# p3_mcu.net
KiCad netlist of a schematic drawn in Altium Designer
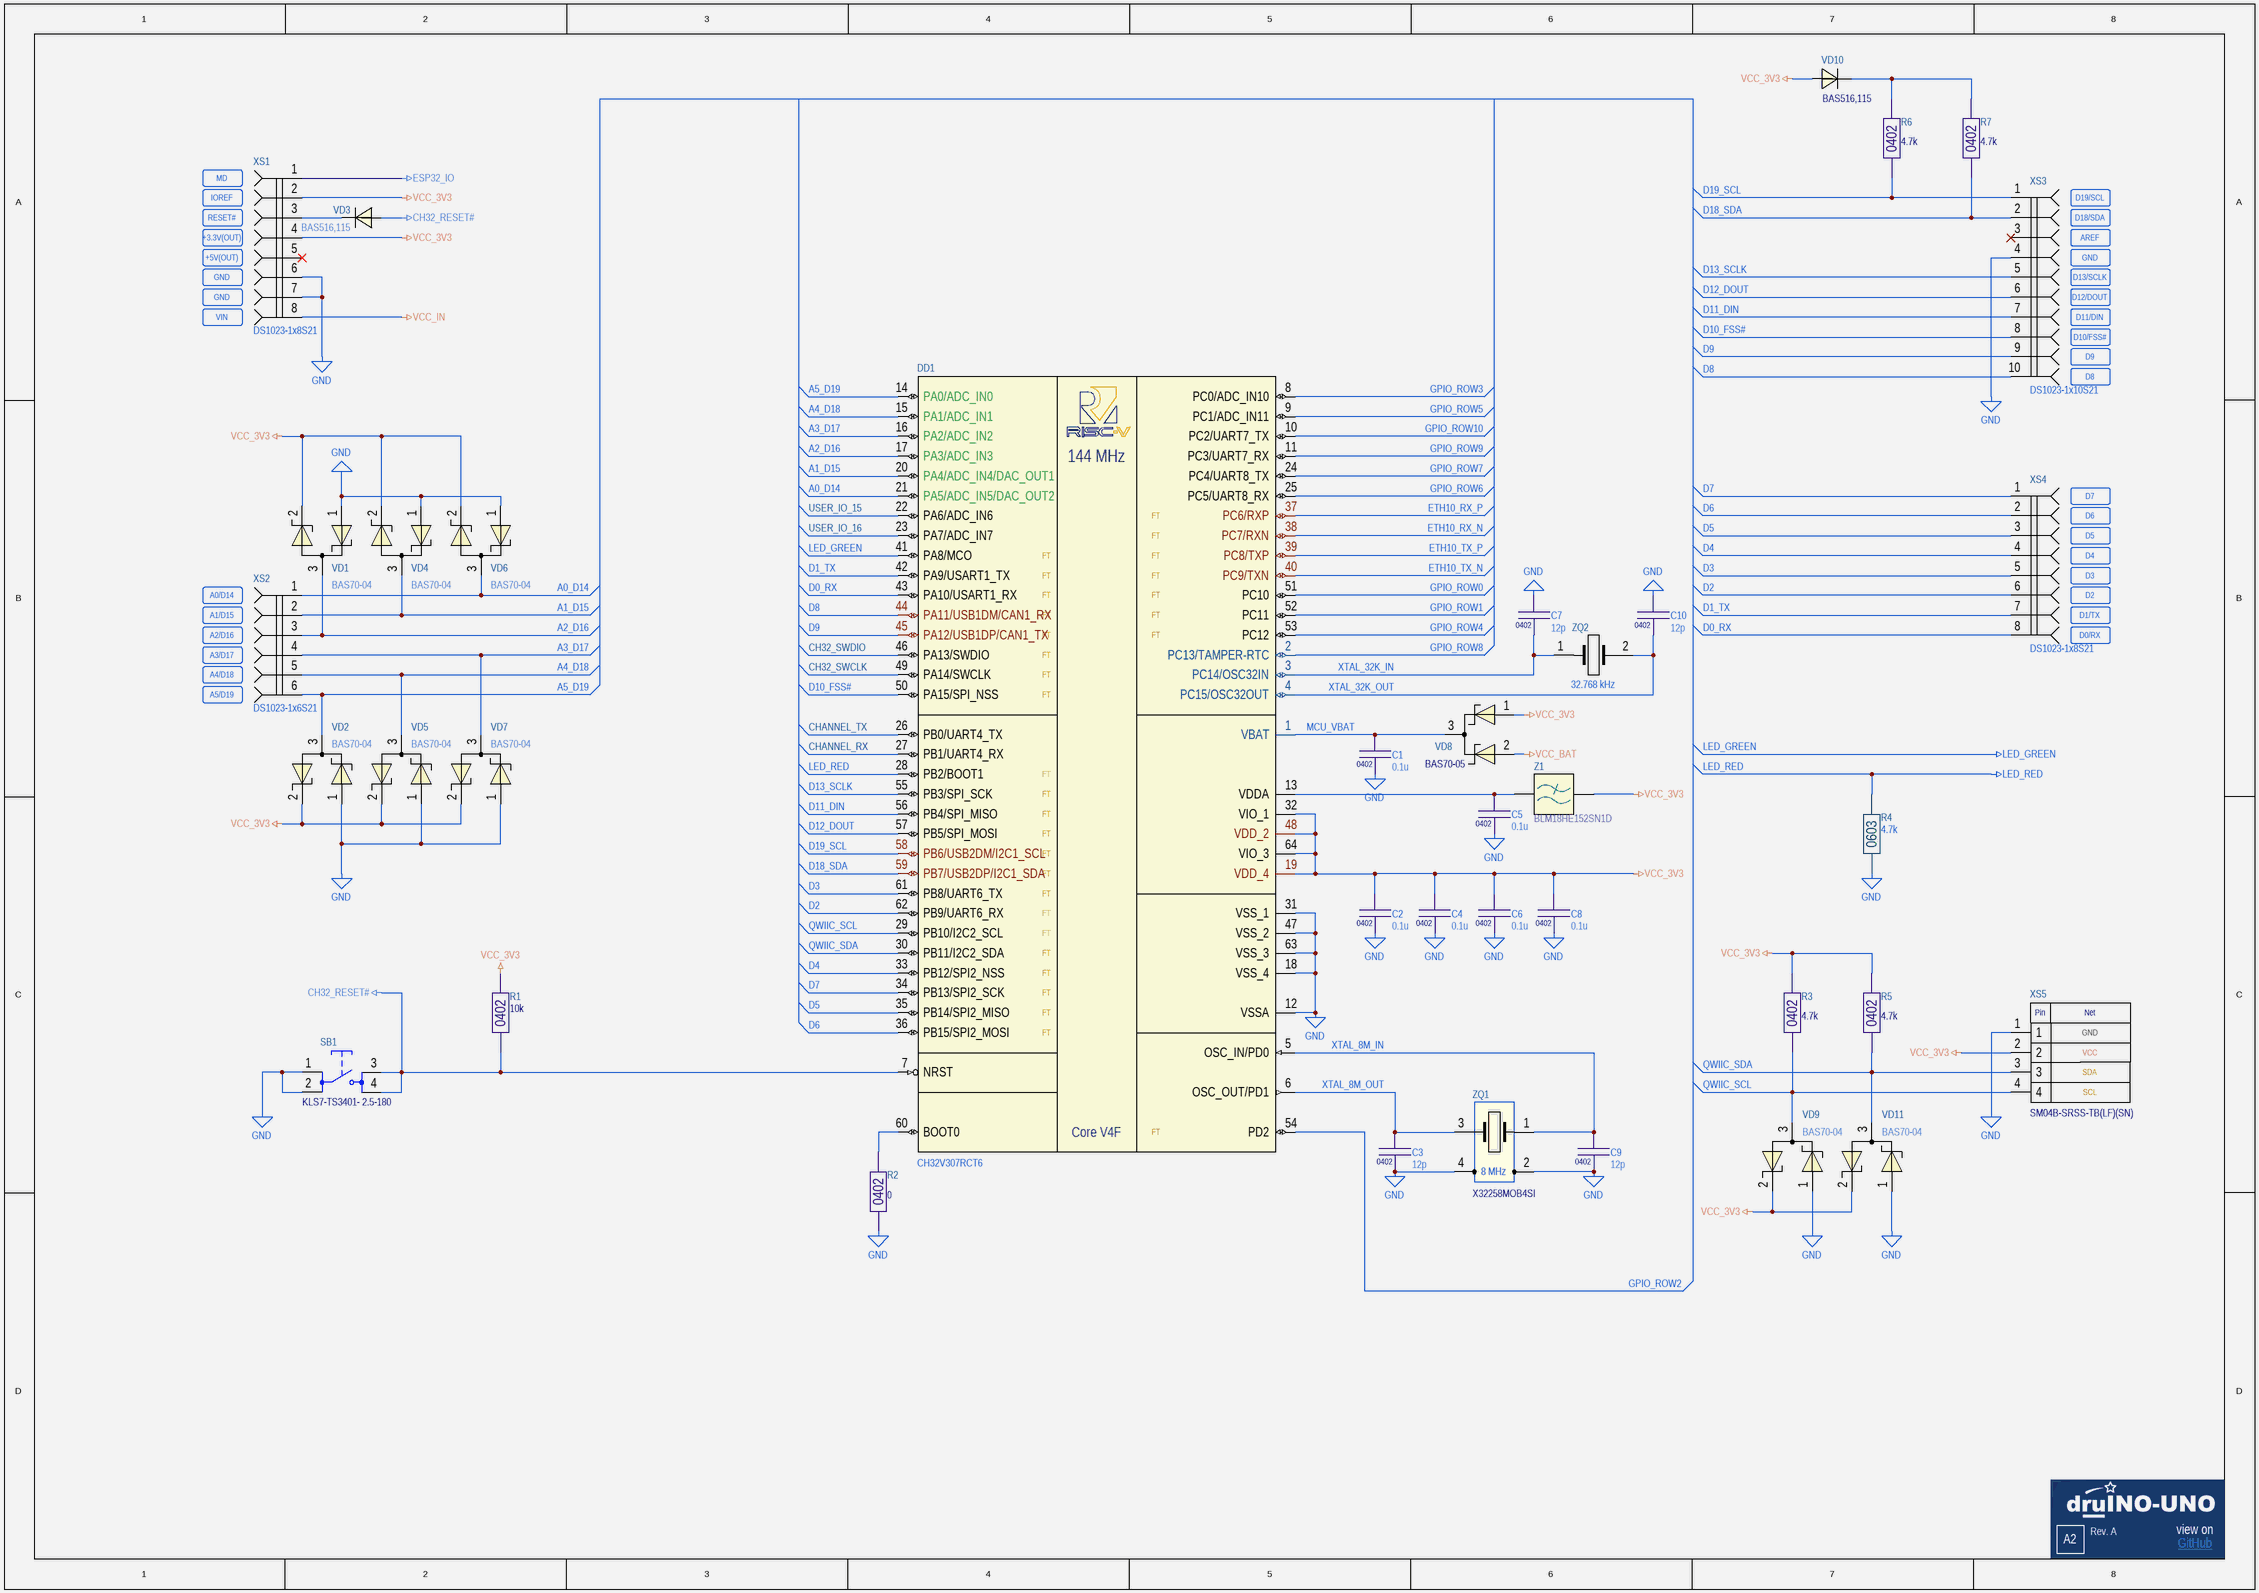
[diagram p0: p3_mcu.SchDoc]

(export (version "E")
  (design (tool "Eeschema 10.0.6"))
  (components
    (comp (ref "C1")
      (value "0.1u")
      (footprint "PcbLib_RC:CAP0402")
      (description "Capacitors 0402 package case")
      (fields
        (field (name "TOLERANCE") "± 5 %")
        (field (name "VOLTAGE") "50 V")
        (field (name "PACKAGE") "0402")
      )
      (libsource (lib "Schlib_RC") (part "C0402"))
    )
    (comp (ref "C2")
      (value "0.1u")
      (footprint "PcbLib_RC:CAP0402")
      (description "Capacitors 0402 package case")
      (fields
        (field (name "TOLERANCE") "± 5 %")
        (field (name "VOLTAGE") "50 V")
        (field (name "PACKAGE") "0402")
      )
      (libsource (lib "Schlib_RC") (part "C0402"))
    )
    (comp (ref "C3")
      (value "12p")
      (footprint "PcbLib_RC:CAP0402")
      (description "Capacitors 0402 package case")
      (fields
        (field (name "TOLERANCE") "± 1 %")
        (field (name "VOLTAGE") "50 V")
        (field (name "PACKAGE") "0402")
      )
      (libsource (lib "Schlib_RC") (part "C0402"))
    )
    (comp (ref "C4")
      (value "0.1u")
      (footprint "PcbLib_RC:CAP0402")
      (description "Capacitors 0402 package case")
      (fields
        (field (name "TOLERANCE") "± 5 %")
        (field (name "VOLTAGE") "50 V")
        (field (name "PACKAGE") "0402")
      )
      (libsource (lib "Schlib_RC") (part "C0402"))
    )
    (comp (ref "C5")
      (value "0.1u")
      (footprint "PcbLib_RC:CAP0402")
      (description "Capacitors 0402 package case")
      (fields
        (field (name "TOLERANCE") "± 5 %")
        (field (name "VOLTAGE") "50 V")
        (field (name "PACKAGE") "0402")
      )
      (libsource (lib "Schlib_RC") (part "C0402"))
    )
    (comp (ref "C6")
      (value "0.1u")
      (footprint "PcbLib_RC:CAP0402")
      (description "Capacitors 0402 package case")
      (fields
        (field (name "TOLERANCE") "± 5 %")
        (field (name "VOLTAGE") "50 V")
        (field (name "PACKAGE") "0402")
      )
      (libsource (lib "Schlib_RC") (part "C0402"))
    )
    (comp (ref "C7")
      (value "12p")
      (footprint "PcbLib_RC:CAP0402")
      (description "Capacitors 0402 package case")
      (fields
        (field (name "TOLERANCE") "± 1 %")
        (field (name "VOLTAGE") "50 V")
        (field (name "PACKAGE") "0402")
      )
      (libsource (lib "Schlib_RC") (part "C0402"))
    )
    (comp (ref "C8")
      (value "0.1u")
      (footprint "PcbLib_RC:CAP0402")
      (description "Capacitors 0402 package case")
      (fields
        (field (name "TOLERANCE") "± 5 %")
        (field (name "VOLTAGE") "50 V")
        (field (name "PACKAGE") "0402")
      )
      (libsource (lib "Schlib_RC") (part "C0402"))
    )
    (comp (ref "C9")
      (value "12p")
      (footprint "PcbLib_RC:CAP0402")
      (description "Capacitors 0402 package case")
      (fields
        (field (name "TOLERANCE") "± 1 %")
        (field (name "VOLTAGE") "50 V")
        (field (name "PACKAGE") "0402")
      )
      (libsource (lib "Schlib_RC") (part "C0402"))
    )
    (comp (ref "C10")
      (value "12p")
      (footprint "PcbLib_RC:CAP0402")
      (description "Capacitors 0402 package case")
      (fields
        (field (name "TOLERANCE") "± 1 %")
        (field (name "VOLTAGE") "50 V")
        (field (name "PACKAGE") "0402")
      )
      (libsource (lib "Schlib_RC") (part "C0402"))
    )
    (comp (ref "DD1")
      (value "CH32V307RCT6")
      (footprint "PcbLib_ICs_part2:LQFP64M")
      (description "RISC-V MCU 144MHz with 256KB flash, 64KB RAM")
      (fields (field (name "MANUFACTURER") "WinChipHead"))
      (libsource (lib "Schlib_WCH") (part "CH32V307RCT6"))
    )
    (comp (ref "R1")
      (value "10k")
      (footprint "PcbLib_RC:RES0402B")
      (description "Resistor 0402 package case")
      (fields
        (field (name "TOLERANCE") "± 1 %")
        (field (name "PART NUMBER") "RC0402FR-0710KL")
        (field (name "PACKAGE") "0402")
      )
      (libsource (lib "Schlib_RC") (part "R0402"))
    )
    (comp (ref "R2")
      (value "0")
      (footprint "PcbLib_RC:RES0402B")
      (description "Resistor 0402 package case")
      (fields
        (field (name "TOLERANCE") "± 1 %")
        (field (name "PART NUMBER") "RC0402FR-070RL")
        (field (name "PACKAGE") "0402")
      )
      (libsource (lib "Schlib_RC") (part "R0402"))
    )
    (comp (ref "R3")
      (value "4.7k")
      (footprint "PcbLib_RC:RES0402B")
      (description "Resistor 0402 package case")
      (fields
        (field (name "TOLERANCE") "± 1 %")
        (field (name "PART NUMBER") "RC0402FR-074K7L")
        (field (name "PACKAGE") "0402")
      )
      (libsource (lib "Schlib_RC") (part "R0402"))
    )
    (comp (ref "R4")
      (value "4.7k")
      (footprint "PcbLib_RC:RES0603B")
      (description "Resistor 0603 package case")
      (fields
        (field (name "TOLERANCE") "± 1 %")
        (field (name "PART NUMBER") "RC0603FR-074K7L")
        (field (name "PACKAGE") "0603")
      )
      (libsource (lib "Schlib_RC") (part "R0603"))
    )
    (comp (ref "R5")
      (value "4.7k")
      (footprint "PcbLib_RC:RES0402B")
      (description "Resistor 0402 package case")
      (fields
        (field (name "TOLERANCE") "± 1 %")
        (field (name "PART NUMBER") "RC0402FR-074K7L")
        (field (name "PACKAGE") "0402")
      )
      (libsource (lib "Schlib_RC") (part "R0402"))
    )
    (comp (ref "R6")
      (value "4.7k")
      (footprint "PcbLib_RC:RES0402B")
      (description "Resistor 0402 package case")
      (fields
        (field (name "TOLERANCE") "± 1 %")
        (field (name "PART NUMBER") "RC0402FR-074K7L")
        (field (name "PACKAGE") "0402")
      )
      (libsource (lib "Schlib_RC") (part "R0402"))
    )
    (comp (ref "R7")
      (value "4.7k")
      (footprint "PcbLib_RC:RES0402B")
      (description "Resistor 0402 package case")
      (fields
        (field (name "TOLERANCE") "± 1 %")
        (field (name "PART NUMBER") "RC0402FR-074K7L")
        (field (name "PACKAGE") "0402")
      )
      (libsource (lib "Schlib_RC") (part "R0402"))
    )
    (comp (ref "SB1")
      (value "KLS7-TS3401- 2.5-180")
      (footprint "PcbLib_Others:TVAF11")
      (description "Tact Button SMD 4х3х2.5mm")
      (fields (field (name "MANUFACTURER") "KLS"))
      (libsource (lib "Schlib_OtherComponents") (part "TVAF11"))
    )
    (comp (ref "VD1")
      (value "BAS70-04")
      (footprint "PcbLib_ICs:SOT23-3")
      (description "Small Signal Schottky Diodes")
      (fields (field (name "MANUFACTURER") "Diodes Incorporated"))
      (libsource (lib "Schlib_Diodes_Incorporated") (part "BAS70-04"))
    )
    (comp (ref "VD2")
      (value "BAS70-04")
      (footprint "PcbLib_ICs:SOT23-3")
      (description "Small Signal Schottky Diodes")
      (fields (field (name "MANUFACTURER") "Diodes Incorporated"))
      (libsource (lib "Schlib_Diodes_Incorporated") (part "BAS70-04"))
    )
    (comp (ref "VD3")
      (value "BAS516,115")
      (footprint "PcbLib_Discrete:SOD-523")
      (description "High-speed switching diode")
      (fields (field (name "MANUFACTURER") "NXP USA Inc."))
      (libsource (lib "Schlib_NXP_Semiconductors") (part "BAS516,115"))
    )
    (comp (ref "VD4")
      (value "BAS70-04")
      (footprint "PcbLib_ICs:SOT23-3")
      (description "Small Signal Schottky Diodes")
      (fields (field (name "MANUFACTURER") "Diodes Incorporated"))
      (libsource (lib "Schlib_Diodes_Incorporated") (part "BAS70-04"))
    )
    (comp (ref "VD5")
      (value "BAS70-04")
      (footprint "PcbLib_ICs:SOT23-3")
      (description "Small Signal Schottky Diodes")
      (fields (field (name "MANUFACTURER") "Diodes Incorporated"))
      (libsource (lib "Schlib_Diodes_Incorporated") (part "BAS70-04"))
    )
    (comp (ref "VD6")
      (value "BAS70-04")
      (footprint "PcbLib_ICs:SOT23-3")
      (description "Small Signal Schottky Diodes")
      (fields (field (name "MANUFACTURER") "Diodes Incorporated"))
      (libsource (lib "Schlib_Diodes_Incorporated") (part "BAS70-04"))
    )
    (comp (ref "VD7")
      (value "BAS70-04")
      (footprint "PcbLib_ICs:SOT23-3")
      (description "Small Signal Schottky Diodes")
      (fields (field (name "MANUFACTURER") "Diodes Incorporated"))
      (libsource (lib "Schlib_Diodes_Incorporated") (part "BAS70-04"))
    )
    (comp (ref "VD8")
      (value "BAS70-05")
      (footprint "PcbLib_ICs:SOT23-3")
      (description "Small Signal Schottky Diodes")
      (fields (field (name "MANUFACTURER") "Diodes Incorporated"))
      (libsource (lib "Schlib_Diodes_Incorporated") (part "BAS70-05"))
    )
    (comp (ref "VD9")
      (value "BAS70-04")
      (footprint "PcbLib_ICs:SOT23-3")
      (description "Small Signal Schottky Diodes")
      (fields (field (name "MANUFACTURER") "Diodes Incorporated"))
      (libsource (lib "Schlib_Diodes_Incorporated") (part "BAS70-04"))
    )
    (comp (ref "VD10")
      (value "BAS516,115")
      (footprint "PcbLib_Discrete:SOD-523")
      (description "High-speed switching diode")
      (fields (field (name "MANUFACTURER") "NXP USA Inc."))
      (libsource (lib "Schlib_NXP_Semiconductors") (part "BAS516,115"))
    )
    (comp (ref "VD11")
      (value "BAS70-04")
      (footprint "PcbLib_ICs:SOT23-3")
      (description "Small Signal Schottky Diodes")
      (fields (field (name "MANUFACTURER") "Diodes Incorporated"))
      (libsource (lib "Schlib_Diodes_Incorporated") (part "BAS70-04"))
    )
    (comp (ref "XS1")
      (value "DS1023-1x8S21")
      (footprint "PcbLib_Pin_Headers_part2:PBS-8(BLUE)")
      (description "2.54mm Female Header V/T Type, H = 8.5mm")
      (fields (field (name "MANUFACTURER") "Connfly"))
      (libsource (lib "Schlib_Connfly") (part "DS1023-1x8S21"))
    )
    (comp (ref "XS2")
      (value "DS1023-1x6S21")
      (footprint "PcbLib_Pin_Headers_part2:PBS-6(blue)")
      (description "2.54mm Female Header V/T Type, H = 8.5mm")
      (fields (field (name "MANUFACTURER") "Connfly"))
      (libsource (lib "Schlib_Connfly") (part "DS1023-1x6S21"))
    )
    (comp (ref "XS3")
      (value "DS1023-1x10S21")
      (footprint "PcbLib_Pin_Headers_part2:PBS-10(BLUE)")
      (description "2.54mm Female Header V/T Type, H = 8.5mm")
      (fields (field (name "MANUFACTURER") "Connfly"))
      (libsource (lib "Schlib_Connfly") (part "DS1023-1x10S21"))
    )
    (comp (ref "XS4")
      (value "DS1023-1x8S21")
      (footprint "PcbLib_Pin_Headers_part2:PBS-8(BLUE)")
      (description "2.54mm Female Header V/T Type, H = 8.5mm")
      (fields (field (name "MANUFACTURER") "Connfly"))
      (libsource (lib "Schlib_Connfly") (part "DS1023-1x8S21"))
    )
    (comp (ref "XS5")
      (value "SM04B-SRSS-TB(LF)(SN)")
      (footprint "PcbLib_Connectors:SM04B-SRSS-TB")
      (description "CONNECTOR, HEADER, SMT, R/A, 1MM, 4WAY")
      (fields (field (name "MANUFACTURER") "JST"))
      (libsource (lib "Schlib_OtherComponents") (part "SM04B-SRSS-TB"))
    )
    (comp (ref "Z1")
      (value "BLM18HE152SN1D")
      (footprint "PcbLib_RC:BLM0603C")
      (description "Power line filter, imperdance 1500 Ohm @100MHz (current 0.5A)")
      (fields (field (name "MANUFACTURER") "Murata"))
      (libsource (lib "Schlib_Murata") (part "BLM18HE152SN1D"))
    )
    (comp (ref "ZQ1")
      (value "X32258MOB4SI")
      (footprint "PcbLib_Others:SMD3225")
      (description "Quartz Crystal 8 MHz")
      (fields (field (name "MANUFACTURER") "YXC"))
      (libsource (lib "Schlib_YXC") (part "X32258MOB4SI"))
    )
    (comp (ref "ZQ2")
      (value "X321532768KGD2SI")
      (footprint "PcbLib_Others:YST310S")
      (description "Quartz Crystal 32768 Hz")
      (fields (field (name "MANUFACTURER") "YXC"))
      (libsource (lib "Schlib_YXC") (part "X321532768KGD2SI"))
    )
  )
  (nets
    (net (code "1") (name "/A0_D14") (class "Default")
      (node (ref "DD1") (pin "21") (pinfunction "PA5/ADC_IN5/DAC_OUT2_21") (pintype "bidirectional"))
      (node (ref "VD6") (pin "3") (pinfunction "A2_3") (pintype "passive"))
      (node (ref "XS2") (pin "1") (pinfunction "1_1") (pintype "passive"))
    )
    (net (code "2") (name "/A1_D15") (class "Default")
      (node (ref "DD1") (pin "20") (pinfunction "PA4/ADC_IN4/DAC_OUT1_20") (pintype "bidirectional"))
      (node (ref "VD4") (pin "3") (pinfunction "A2_3") (pintype "passive"))
      (node (ref "XS2") (pin "2") (pinfunction "2_2") (pintype "passive"))
    )
    (net (code "3") (name "/A2_D16") (class "Default")
      (node (ref "DD1") (pin "17") (pinfunction "PA3/ADC_IN3_17") (pintype "bidirectional"))
      (node (ref "VD1") (pin "3") (pinfunction "A2_3") (pintype "passive"))
      (node (ref "XS2") (pin "3") (pinfunction "3_3") (pintype "passive"))
    )
    (net (code "4") (name "/A3_D17") (class "Default")
      (node (ref "DD1") (pin "16") (pinfunction "PA2/ADC_IN2_16") (pintype "bidirectional"))
      (node (ref "VD7") (pin "3") (pinfunction "A2_3") (pintype "passive"))
      (node (ref "XS2") (pin "4") (pinfunction "4_4") (pintype "passive"))
    )
    (net (code "5") (name "/A4_D18") (class "Default")
      (node (ref "DD1") (pin "15") (pinfunction "PA1/ADC_IN1_15") (pintype "bidirectional"))
      (node (ref "VD5") (pin "3") (pinfunction "A2_3") (pintype "passive"))
      (node (ref "XS2") (pin "5") (pinfunction "5_5") (pintype "passive"))
    )
    (net (code "6") (name "/A5_D19") (class "Default")
      (node (ref "DD1") (pin "14") (pinfunction "PA0/ADC_IN0_14") (pintype "bidirectional"))
      (node (ref "VD2") (pin "3") (pinfunction "A2_3") (pintype "passive"))
      (node (ref "XS2") (pin "6") (pinfunction "6_6") (pintype "passive"))
    )
    (net (code "7") (name "/CH32_SWCLK") (class "Default")
      (node (ref "DD1") (pin "49") (pinfunction "PA14/SWCLK_49") (pintype "bidirectional"))
    )
    (net (code "8") (name "/CH32_SWDIO") (class "Default")
      (node (ref "DD1") (pin "46") (pinfunction "PA13/SWDIO_46") (pintype "bidirectional"))
    )
    (net (code "9") (name "/CHANNEL_RX") (class "Default")
      (node (ref "DD1") (pin "27") (pinfunction "PB1/UART4_RX_27") (pintype "bidirectional"))
    )
    (net (code "10") (name "/CHANNEL_TX") (class "Default")
      (node (ref "DD1") (pin "26") (pinfunction "PB0/UART4_TX_26") (pintype "bidirectional"))
    )
    (net (code "11") (name "/D0_RX") (class "Default")
      (node (ref "DD1") (pin "43") (pinfunction "PA10/USART1_RX_43") (pintype "bidirectional"))
      (node (ref "XS4") (pin "8") (pinfunction "8_8") (pintype "passive"))
    )
    (net (code "12") (name "/D1_TX") (class "Default")
      (node (ref "DD1") (pin "42") (pinfunction "PA9/USART1_TX_42") (pintype "bidirectional"))
      (node (ref "XS4") (pin "7") (pinfunction "7_7") (pintype "passive"))
    )
    (net (code "13") (name "/D2") (class "Default")
      (node (ref "DD1") (pin "62") (pinfunction "PB9/UART6_RX_62") (pintype "bidirectional"))
      (node (ref "XS4") (pin "6") (pinfunction "6_6") (pintype "passive"))
    )
    (net (code "14") (name "/D3") (class "Default")
      (node (ref "DD1") (pin "61") (pinfunction "PB8/UART6_TX_61") (pintype "bidirectional"))
      (node (ref "XS4") (pin "5") (pinfunction "5_5") (pintype "passive"))
    )
    (net (code "15") (name "/D4") (class "Default")
      (node (ref "DD1") (pin "33") (pinfunction "PB12/SPI2_NSS_33") (pintype "bidirectional"))
      (node (ref "XS4") (pin "4") (pinfunction "4_4") (pintype "passive"))
    )
    (net (code "16") (name "/D5") (class "Default")
      (node (ref "DD1") (pin "35") (pinfunction "PB14/SPI2_MISO_35") (pintype "bidirectional"))
      (node (ref "XS4") (pin "3") (pinfunction "3_3") (pintype "passive"))
    )
    (net (code "17") (name "/D6") (class "Default")
      (node (ref "DD1") (pin "36") (pinfunction "PB15/SPI2_MOSI_36") (pintype "bidirectional"))
      (node (ref "XS4") (pin "2") (pinfunction "2_2") (pintype "passive"))
    )
    (net (code "18") (name "/D7") (class "Default")
      (node (ref "DD1") (pin "34") (pinfunction "PB13/SPI2_SCK_34") (pintype "bidirectional"))
      (node (ref "XS4") (pin "1") (pinfunction "1_1") (pintype "passive"))
    )
    (net (code "19") (name "/D8") (class "Default")
      (node (ref "DD1") (pin "44") (pinfunction "PA11/USB1DM/CAN1_RX_44") (pintype "bidirectional"))
      (node (ref "XS3") (pin "10") (pinfunction "10_10") (pintype "passive"))
    )
    (net (code "20") (name "/D9") (class "Default")
      (node (ref "DD1") (pin "45") (pinfunction "PA12/USB1DP/CAN1_TX_45") (pintype "bidirectional"))
      (node (ref "XS3") (pin "9") (pinfunction "9_9") (pintype "passive"))
    )
    (net (code "21") (name "/D10_FSS#") (class "Default")
      (node (ref "DD1") (pin "50") (pinfunction "PA15/SPI_NSS_50") (pintype "bidirectional"))
      (node (ref "XS3") (pin "8") (pinfunction "8_8") (pintype "passive"))
    )
    (net (code "22") (name "/D11_DIN") (class "Default")
      (node (ref "DD1") (pin "56") (pinfunction "PB4/SPI_MISO_56") (pintype "bidirectional"))
      (node (ref "XS3") (pin "7") (pinfunction "7_7") (pintype "passive"))
    )
    (net (code "23") (name "/D12_DOUT") (class "Default")
      (node (ref "DD1") (pin "57") (pinfunction "PB5/SPI_MOSI_57") (pintype "bidirectional"))
      (node (ref "XS3") (pin "6") (pinfunction "6_6") (pintype "passive"))
    )
    (net (code "24") (name "/D13_SCLK") (class "Default")
      (node (ref "DD1") (pin "55") (pinfunction "PB3/SPI_SCK_55") (pintype "bidirectional"))
      (node (ref "XS3") (pin "5") (pinfunction "5_5") (pintype "passive"))
    )
    (net (code "25") (name "/D18_SDA") (class "Default")
      (node (ref "DD1") (pin "59") (pinfunction "PB7/USB2DP/I2C1_SDA_59") (pintype "bidirectional"))
      (node (ref "R7") (pin "2") (pinfunction "2_2") (pintype "passive"))
      (node (ref "XS3") (pin "2") (pinfunction "2_2") (pintype "passive"))
    )
    (net (code "26") (name "/D19_SCL") (class "Default")
      (node (ref "DD1") (pin "58") (pinfunction "PB6/USB2DM/I2C1_SCL_58") (pintype "bidirectional"))
      (node (ref "R6") (pin "2") (pinfunction "2_2") (pintype "passive"))
      (node (ref "XS3") (pin "1") (pinfunction "1_1") (pintype "passive"))
    )
    (net (code "27") (name "/ETH10_RX_N") (class "Default")
      (node (ref "DD1") (pin "38") (pinfunction "PC7/RXN_38") (pintype "bidirectional"))
    )
    (net (code "28") (name "/ETH10_RX_P") (class "Default")
      (node (ref "DD1") (pin "37") (pinfunction "PC6/RXP_37") (pintype "bidirectional"))
    )
    (net (code "29") (name "/ETH10_TX_N") (class "Default")
      (node (ref "DD1") (pin "40") (pinfunction "PC9/TXN_40") (pintype "bidirectional"))
    )
    (net (code "30") (name "/ETH10_TX_P") (class "Default")
      (node (ref "DD1") (pin "39") (pinfunction "PC8/TXP_39") (pintype "bidirectional"))
    )
    (net (code "31") (name "/GPIO_ROW0") (class "Default")
      (node (ref "DD1") (pin "51") (pinfunction "PC10_51") (pintype "bidirectional"))
    )
    (net (code "32") (name "/GPIO_ROW1") (class "Default")
      (node (ref "DD1") (pin "52") (pinfunction "PC11_52") (pintype "bidirectional"))
    )
    (net (code "33") (name "/GPIO_ROW2") (class "Default")
      (node (ref "DD1") (pin "54") (pinfunction "PD2_54") (pintype "bidirectional"))
    )
    (net (code "34") (name "/GPIO_ROW3") (class "Default")
      (node (ref "DD1") (pin "8") (pinfunction "PC0/ADC_IN10_8") (pintype "bidirectional"))
    )
    (net (code "35") (name "/GPIO_ROW4") (class "Default")
      (node (ref "DD1") (pin "53") (pinfunction "PC12_53") (pintype "bidirectional"))
    )
    (net (code "36") (name "/GPIO_ROW5") (class "Default")
      (node (ref "DD1") (pin "9") (pinfunction "PC1/ADC_IN11_9") (pintype "bidirectional"))
    )
    (net (code "37") (name "/GPIO_ROW6") (class "Default")
      (node (ref "DD1") (pin "25") (pinfunction "PC5/UART8_RX_25") (pintype "bidirectional"))
    )
    (net (code "38") (name "/GPIO_ROW7") (class "Default")
      (node (ref "DD1") (pin "24") (pinfunction "PC4/UART8_TX_24") (pintype "bidirectional"))
    )
    (net (code "39") (name "/GPIO_ROW8") (class "Default")
      (node (ref "DD1") (pin "2") (pinfunction "PC13/TAMPER-RTC_2") (pintype "bidirectional"))
    )
    (net (code "40") (name "/GPIO_ROW9") (class "Default")
      (node (ref "DD1") (pin "11") (pinfunction "PC3/UART7_RX_11") (pintype "bidirectional"))
    )
    (net (code "41") (name "/GPIO_ROW10") (class "Default")
      (node (ref "DD1") (pin "10") (pinfunction "PC2/UART7_TX_10") (pintype "bidirectional"))
    )
    (net (code "42") (name "/MCU_VBAT") (class "Default")
      (node (ref "C1") (pin "1") (pinfunction "1_1") (pintype "passive"))
      (node (ref "DD1") (pin "1") (pinfunction "VBAT_1") (pintype "power_in"))
      (node (ref "VD8") (pin "3") (pinfunction "A2_3") (pintype "passive"))
    )
    (net (code "43") (name "/QWIIC_SCL") (class "Default")
      (node (ref "DD1") (pin "29") (pinfunction "PB10/I2C2_SCL_29") (pintype "bidirectional"))
      (node (ref "R3") (pin "2") (pinfunction "2_2") (pintype "passive"))
      (node (ref "VD9") (pin "3") (pinfunction "A2_3") (pintype "passive"))
      (node (ref "XS5") (pin "4") (pinfunction "4_4") (pintype "passive"))
    )
    (net (code "44") (name "/QWIIC_SDA") (class "Default")
      (node (ref "DD1") (pin "30") (pinfunction "PB11/I2C2_SDA_30") (pintype "bidirectional"))
      (node (ref "R5") (pin "2") (pinfunction "2_2") (pintype "passive"))
      (node (ref "VD11") (pin "3") (pinfunction "A2_3") (pintype "passive"))
      (node (ref "XS5") (pin "3") (pinfunction "3_3") (pintype "passive"))
    )
    (net (code "45") (name "/USER_IO_15") (class "Default")
      (node (ref "DD1") (pin "22") (pinfunction "PA6/ADC_IN6_22") (pintype "bidirectional"))
    )
    (net (code "46") (name "/USER_IO_16") (class "Default")
      (node (ref "DD1") (pin "23") (pinfunction "PA7/ADC_IN7_23") (pintype "bidirectional"))
    )
    (net (code "47") (name "/XTAL_8M_IN") (class "Default")
      (node (ref "C9") (pin "1") (pinfunction "1_1") (pintype "passive"))
      (node (ref "DD1") (pin "5") (pinfunction "OSC_IN/PD0_5") (pintype "input"))
      (node (ref "ZQ1") (pin "1") (pinfunction "XTAL0_1") (pintype "passive"))
    )
    (net (code "48") (name "/XTAL_8M_OUT") (class "Default")
      (node (ref "C3") (pin "1") (pinfunction "1_1") (pintype "passive"))
      (node (ref "DD1") (pin "6") (pinfunction "OSC_OUT/PD1_6") (pintype "output"))
      (node (ref "ZQ1") (pin "3") (pinfunction "XTAL1_3") (pintype "passive"))
    )
    (net (code "49") (name "/XTAL_32K_IN") (class "Default")
      (node (ref "C7") (pin "2") (pinfunction "2_2") (pintype "passive"))
      (node (ref "DD1") (pin "3") (pinfunction "PC14/OSC32IN_3") (pintype "bidirectional"))
      (node (ref "ZQ2") (pin "1") (pinfunction "XTAL0_1") (pintype "passive"))
    )
    (net (code "50") (name "/XTAL_32K_OUT") (class "Default")
      (node (ref "C10") (pin "2") (pinfunction "2_2") (pintype "passive"))
      (node (ref "DD1") (pin "4") (pinfunction "PC15/OSC32OUT_4") (pintype "bidirectional"))
      (node (ref "ZQ2") (pin "2") (pinfunction "XTAL1_2") (pintype "passive"))
    )
    (net (code "51") (name "CH32_RESET#") (class "Default")
      (node (ref "DD1") (pin "7") (pinfunction "NRST_7") (pintype "input"))
      (node (ref "R1") (pin "2") (pinfunction "2_2") (pintype "passive"))
      (node (ref "SB1") (pin "3") (pinfunction "3_3") (pintype "passive"))
      (node (ref "SB1") (pin "4") (pinfunction "4_4") (pintype "passive"))
      (node (ref "VD3") (pin "2") (pinfunction "2_2") (pintype "passive"))
    )
    (net (code "52") (name "ESP32_IO") (class "Default")
      (node (ref "XS1") (pin "1") (pinfunction "1_1") (pintype "passive"))
    )
    (net (code "53") (name "GND") (class "Default")
      (node (ref "C1") (pin "2") (pinfunction "2_2") (pintype "passive"))
      (node (ref "C10") (pin "1") (pinfunction "1_1") (pintype "passive"))
      (node (ref "C2") (pin "2") (pinfunction "2_2") (pintype "passive"))
      (node (ref "C3") (pin "2") (pinfunction "2_2") (pintype "passive"))
      (node (ref "C4") (pin "2") (pinfunction "2_2") (pintype "passive"))
      (node (ref "C5") (pin "2") (pinfunction "2_2") (pintype "passive"))
      (node (ref "C6") (pin "2") (pinfunction "2_2") (pintype "passive"))
      (node (ref "C7") (pin "1") (pinfunction "1_1") (pintype "passive"))
      (node (ref "C8") (pin "2") (pinfunction "2_2") (pintype "passive"))
      (node (ref "C9") (pin "2") (pinfunction "2_2") (pintype "passive"))
      (node (ref "DD1") (pin "12") (pinfunction "VSSA_12") (pintype "power_in"))
      (node (ref "DD1") (pin "18") (pinfunction "VSS_4_18") (pintype "power_in"))
      (node (ref "DD1") (pin "31") (pinfunction "VSS_1_31") (pintype "power_in"))
      (node (ref "DD1") (pin "47") (pinfunction "VSS_2_47") (pintype "power_in"))
      (node (ref "DD1") (pin "63") (pinfunction "VSS_3_63") (pintype "power_in"))
      (node (ref "R2") (pin "2") (pinfunction "2_2") (pintype "passive"))
      (node (ref "R4") (pin "2") (pinfunction "2_2") (pintype "passive"))
      (node (ref "SB1") (pin "1") (pinfunction "1_1") (pintype "passive"))
      (node (ref "SB1") (pin "2") (pinfunction "2_2") (pintype "passive"))
      (node (ref "VD1") (pin "1") (pinfunction "A1_1") (pintype "passive"))
      (node (ref "VD11") (pin "1") (pinfunction "A1_1") (pintype "passive"))
      (node (ref "VD2") (pin "1") (pinfunction "A1_1") (pintype "passive"))
      (node (ref "VD4") (pin "1") (pinfunction "A1_1") (pintype "passive"))
      (node (ref "VD5") (pin "1") (pinfunction "A1_1") (pintype "passive"))
      (node (ref "VD6") (pin "1") (pinfunction "A1_1") (pintype "passive"))
      (node (ref "VD7") (pin "1") (pinfunction "A1_1") (pintype "passive"))
      (node (ref "VD9") (pin "1") (pinfunction "A1_1") (pintype "passive"))
      (node (ref "XS1") (pin "6") (pinfunction "6_6") (pintype "passive"))
      (node (ref "XS1") (pin "7") (pinfunction "7_7") (pintype "passive"))
      (node (ref "XS3") (pin "4") (pinfunction "4_4") (pintype "passive"))
      (node (ref "XS5") (pin "1") (pinfunction "1_1") (pintype "passive"))
      (node (ref "ZQ1") (pin "2") (pinfunction "GND_2") (pintype "power_in"))
      (node (ref "ZQ1") (pin "4") (pinfunction "GND_4") (pintype "power_in"))
    )
    (net (code "54") (name "LED_GREEN") (class "Default")
      (node (ref "DD1") (pin "41") (pinfunction "PA8/MCO_41") (pintype "bidirectional"))
    )
    (net (code "55") (name "LED_RED") (class "Default")
      (node (ref "DD1") (pin "28") (pinfunction "PB2/BOOT1_28") (pintype "bidirectional"))
      (node (ref "R4") (pin "1") (pinfunction "1_1") (pintype "passive"))
    )
    (net (code "56") (name "Net-(DD1-BOOT0)") (class "Default")
      (node (ref "DD1") (pin "60") (pinfunction "BOOT0_60") (pintype "bidirectional"))
      (node (ref "R2") (pin "1") (pinfunction "1_1") (pintype "passive"))
    )
    (net (code "57") (name "Net-(DD1-VDDA)") (class "Default")
      (node (ref "C5") (pin "1") (pinfunction "1_1") (pintype "passive"))
      (node (ref "DD1") (pin "13") (pinfunction "VDDA_13") (pintype "power_in"))
      (node (ref "Z1") (pin "2") (pinfunction "2_2") (pintype "passive"))
    )
    (net (code "58") (name "Net-(R6-Pad1)") (class "Default")
      (node (ref "R6") (pin "1") (pinfunction "1_1") (pintype "passive"))
      (node (ref "R7") (pin "1") (pinfunction "1_1") (pintype "passive"))
      (node (ref "VD10") (pin "1") (pinfunction "1_1") (pintype "passive"))
    )
    (net (code "59") (name "Net-(VD3-Pad1)") (class "Default")
      (node (ref "VD3") (pin "1") (pinfunction "1_1") (pintype "passive"))
      (node (ref "XS1") (pin "3") (pinfunction "3_3") (pintype "passive"))
    )
    (net (code "60") (name "VCC_3V3") (class "Default")
      (node (ref "C2") (pin "1") (pinfunction "1_1") (pintype "passive"))
      (node (ref "C4") (pin "1") (pinfunction "1_1") (pintype "passive"))
      (node (ref "C6") (pin "1") (pinfunction "1_1") (pintype "passive"))
      (node (ref "C8") (pin "1") (pinfunction "1_1") (pintype "passive"))
      (node (ref "DD1") (pin "19") (pinfunction "VDD_4_19") (pintype "power_in"))
      (node (ref "DD1") (pin "32") (pinfunction "VIO_1_32") (pintype "power_in"))
      (node (ref "DD1") (pin "48") (pinfunction "VDD_2_48") (pintype "power_in"))
      (node (ref "DD1") (pin "64") (pinfunction "VIO_3_64") (pintype "power_in"))
      (node (ref "R1") (pin "1") (pinfunction "1_1") (pintype "passive"))
      (node (ref "R3") (pin "1") (pinfunction "1_1") (pintype "passive"))
      (node (ref "R5") (pin "1") (pinfunction "1_1") (pintype "passive"))
      (node (ref "VD1") (pin "2") (pinfunction "C_2") (pintype "passive"))
      (node (ref "VD10") (pin "2") (pinfunction "2_2") (pintype "passive"))
      (node (ref "VD11") (pin "2") (pinfunction "C_2") (pintype "passive"))
      (node (ref "VD2") (pin "2") (pinfunction "C_2") (pintype "passive"))
      (node (ref "VD4") (pin "2") (pinfunction "C_2") (pintype "passive"))
      (node (ref "VD5") (pin "2") (pinfunction "C_2") (pintype "passive"))
      (node (ref "VD6") (pin "2") (pinfunction "C_2") (pintype "passive"))
      (node (ref "VD7") (pin "2") (pinfunction "C_2") (pintype "passive"))
      (node (ref "VD8") (pin "1") (pinfunction "A1_1") (pintype "passive"))
      (node (ref "VD9") (pin "2") (pinfunction "C_2") (pintype "passive"))
      (node (ref "XS1") (pin "2") (pinfunction "2_2") (pintype "passive"))
      (node (ref "XS1") (pin "4") (pinfunction "4_4") (pintype "passive"))
      (node (ref "XS5") (pin "2") (pinfunction "2_2") (pintype "passive"))
      (node (ref "Z1") (pin "1") (pinfunction "1_1") (pintype "passive"))
    )
    (net (code "61") (name "VCC_BAT") (class "Default")
      (node (ref "VD8") (pin "2") (pinfunction "C_2") (pintype "passive"))
    )
    (net (code "62") (name "VCC_IN") (class "Default")
      (node (ref "XS1") (pin "8") (pinfunction "8_8") (pintype "passive"))
    )
    (net (code "63") (name "unconnected-(XS1-Pad5)") (class "Default")
      (node (ref "XS1") (pin "5") (pinfunction "5_5") (pintype "passive+no_connect"))
    )
    (net (code "64") (name "unconnected-(XS3-Pad3)") (class "Default")
      (node (ref "XS3") (pin "3") (pinfunction "3_3") (pintype "passive+no_connect"))
    )
  )
)
